# 06_Ethernet_Interface.net
KiCad netlist of a schematic drawn in Altium Designer
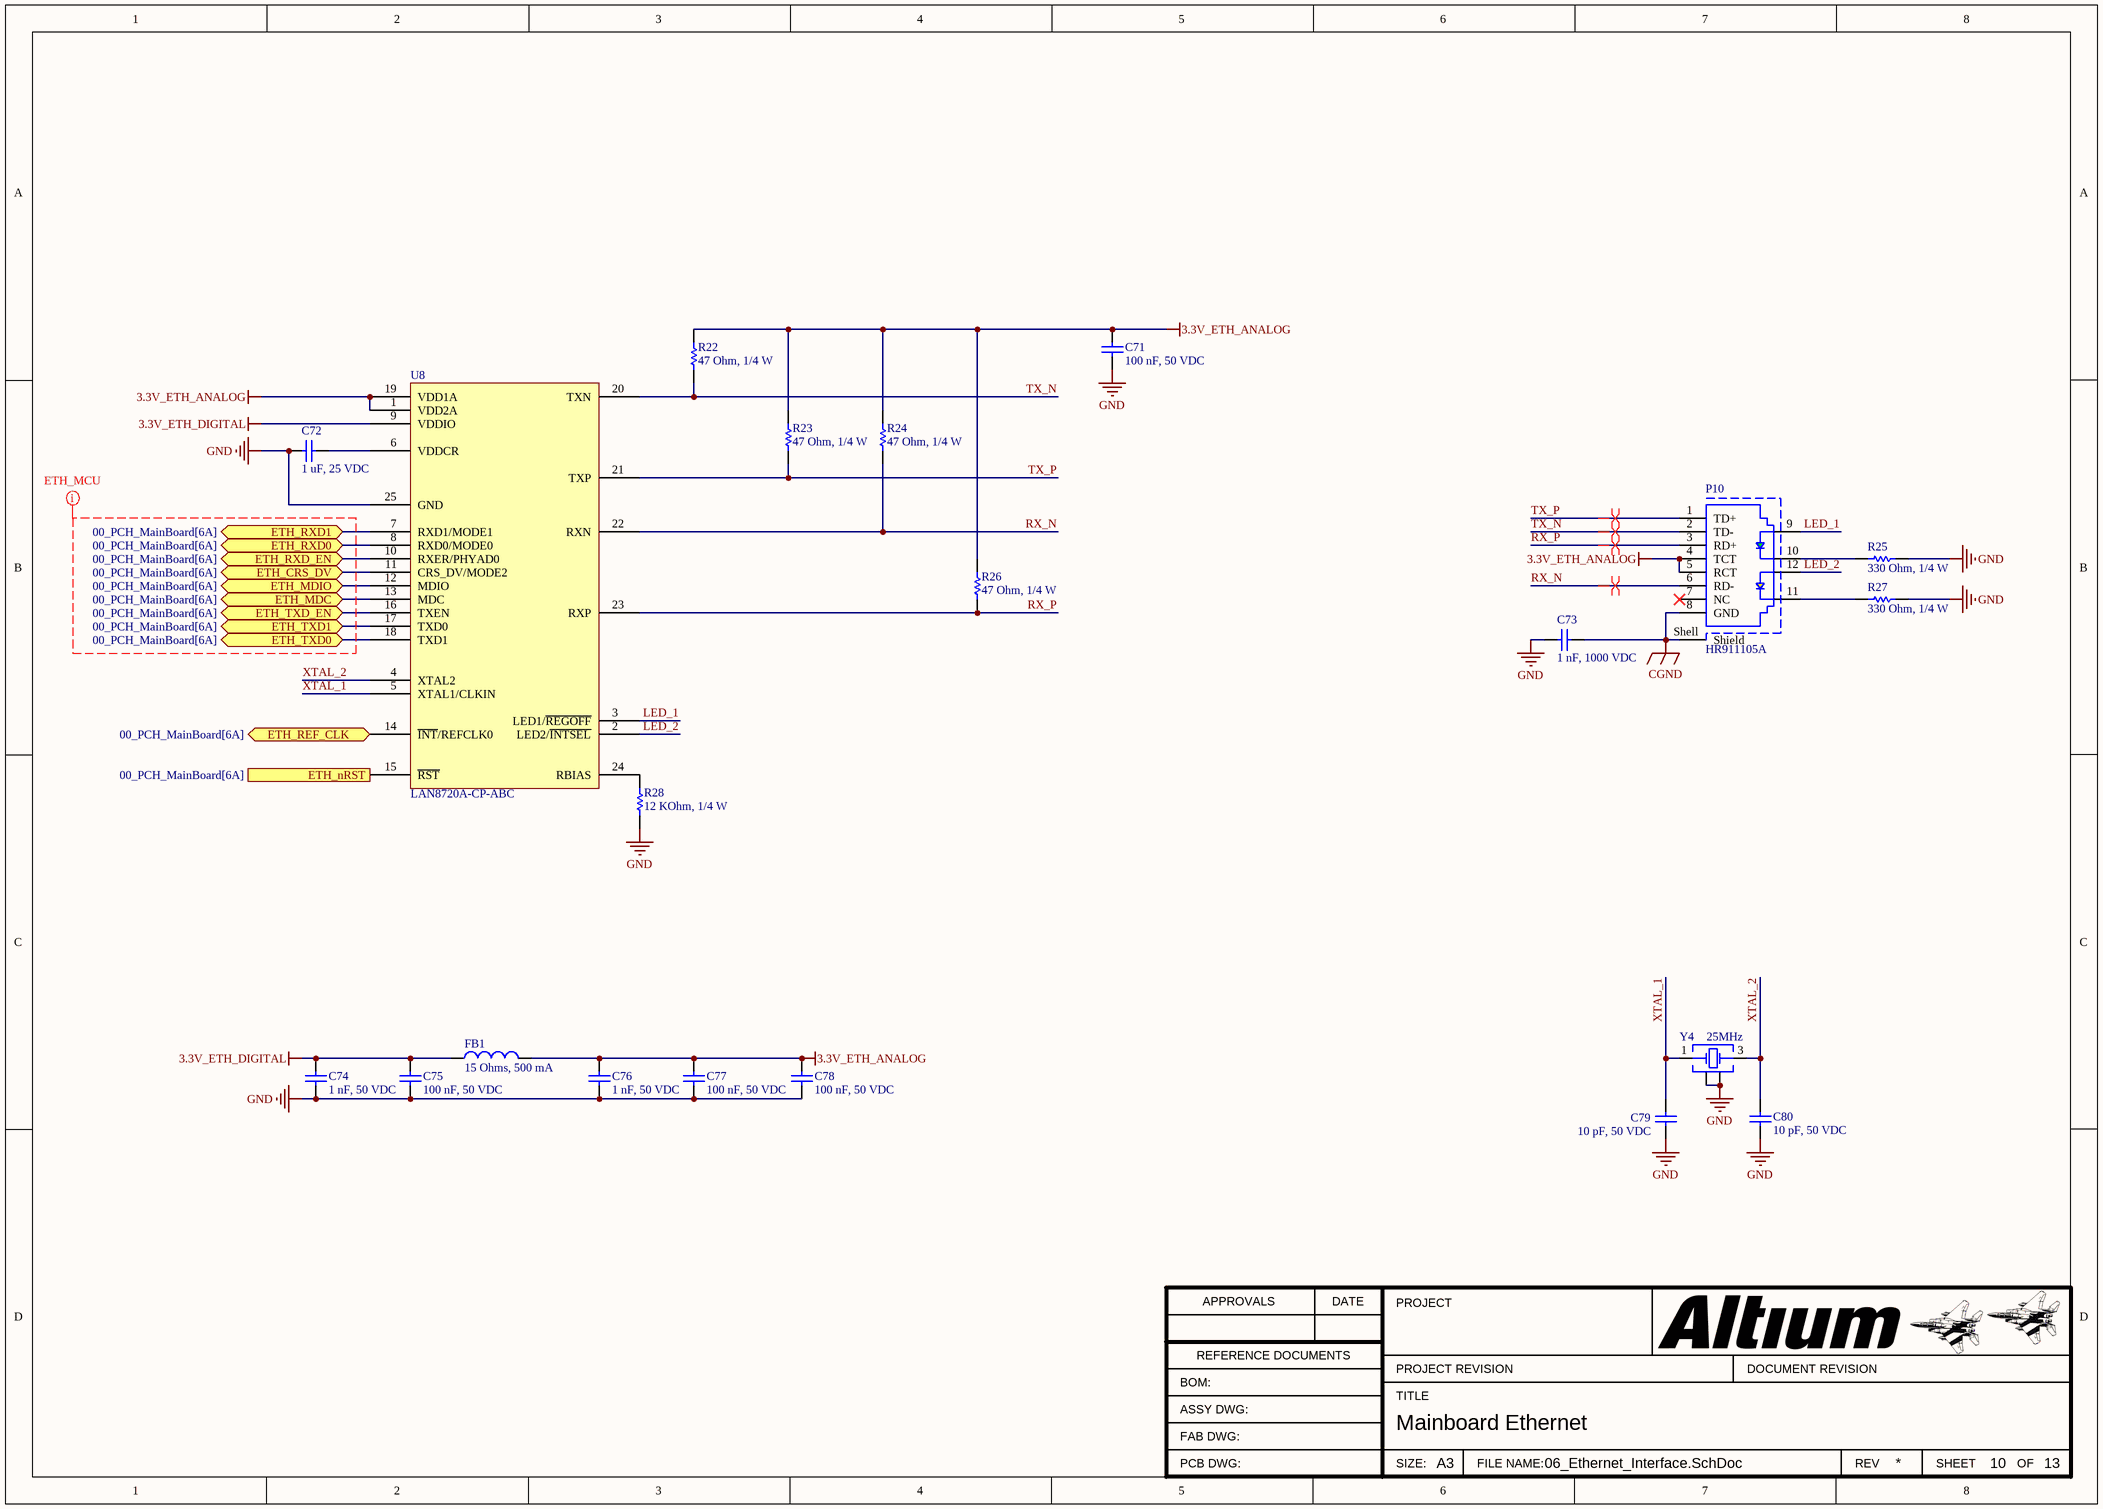
[diagram p0: 06_Ethernet_Interface.SchDoc]

(export (version "E")
  (design (tool "Eeschema 10.0.6"))
  (components
    (comp (ref "C71")
      (value "100 nF, 50 VDC")
      (footprint "CAP_0603")
      (description "CAP, size 0603, 100 nF, 50 VDC")
      (fields (field (name "TOLERANCE") "+/-10%"))
      (libsource (lib "Altium_Ceramic_Cap") (part "0106031041050"))
    )
    (comp (ref "C72")
      (value "1 uF, 25 VDC")
      (footprint "CAP_0603")
      (description "CAP, size 0603, 1 uF, 25 VDC")
      (fields (field (name "TOLERANCE") "+/-10%"))
      (libsource (lib "Altium_Ceramic_Cap") (part "0106031051025"))
    )
    (comp (ref "C73")
      (value "1 nF, 1000 VDC")
      (footprint "CAP1210")
      (description "CAP, size 1210, 1nF, 1000 VDC")
      (fields (field (name "TOLERANCE") "+/-10%"))
      (libsource (lib "Altium_Ceramic_Cap") (part "011210102101000"))
    )
    (comp (ref "C74")
      (value "1 nF, 50 VDC")
      (footprint "CAP_0603")
      (description "CAP, size 0603, 1 nF, 50 VDC")
      (fields (field (name "TOLERANCE") "+/-10%"))
      (libsource (lib "Altium_Ceramic_Cap") (part "0106031051050"))
    )
    (comp (ref "C75")
      (value "100 nF, 50 VDC")
      (footprint "CAP_0603")
      (description "CAP, size 0603, 100 nF, 50 VDC")
      (fields (field (name "TOLERANCE") "+/-10%"))
      (libsource (lib "Altium_Ceramic_Cap") (part "0106031041050"))
    )
    (comp (ref "C76")
      (value "1 nF, 50 VDC")
      (footprint "CAP_0603")
      (description "CAP, size 0603, 1 nF, 50 VDC")
      (fields (field (name "TOLERANCE") "+/-10%"))
      (libsource (lib "Altium_Ceramic_Cap") (part "0106031051050"))
    )
    (comp (ref "C77")
      (value "100 nF, 50 VDC")
      (footprint "CAP_0603")
      (description "CAP, size 0603, 100 nF, 50 VDC")
      (fields (field (name "TOLERANCE") "+/-10%"))
      (libsource (lib "Altium_Ceramic_Cap") (part "0106031041050"))
    )
    (comp (ref "C78")
      (value "100 nF, 50 VDC")
      (footprint "CAP_0603")
      (description "CAP, size 0603, 100 nF, 50 VDC")
      (fields (field (name "TOLERANCE") "+/-10%"))
      (libsource (lib "Altium_Ceramic_Cap") (part "0106031041050"))
    )
    (comp (ref "C79")
      (value "10 pF, 50 VDC")
      (footprint "CAP_0603")
      (description "CAP, size 0603, 10 pF, 50 VDC")
      (fields (field (name "TOLERANCE") "+/-5%"))
      (libsource (lib "Altium_Ceramic_Cap") (part "0106031000550"))
    )
    (comp (ref "C80")
      (value "10 pF, 50 VDC")
      (footprint "CAP_0603")
      (description "CAP, size 0603, 10 pF, 50 VDC")
      (fields (field (name "TOLERANCE") "+/-5%"))
      (libsource (lib "Altium_Ceramic_Cap") (part "0106031000550"))
    )
    (comp (ref "FB1")
      (value "15 Ohms, 500 mA")
      (footprint "FER_0603")
      (description "Ferrite, 0603, 15 Ohms, 500 mA")
      (fields (field (name "TOLERANCE") "+/-25%"))
      (libsource (lib "Altium_Ferrite_Bead") (part "03060315050125"))
    )
    (comp (ref "P10")
      (value "HR911105A")
      (footprint "HANRUN_HR911105A")
      (description "Single Port RJ45 Connector with Integrated Magnetics and LED")
      (libsource (lib "Altium_Other") (part "HANRUN_HR911105A"))
    )
    (comp (ref "R22")
      (value "47 Ohm, 1/4 W")
      (footprint "resistor_0603")
      (description "RES, size 0603, 47 Ohm, 1/4 W")
      (libsource (lib "Altium_Resistor") (part "0006034701"))
    )
    (comp (ref "R23")
      (value "47 Ohm, 1/4 W")
      (footprint "resistor_0603")
      (description "RES, size 0603, 47 Ohm, 1/4 W")
      (libsource (lib "Altium_Resistor") (part "0006034701"))
    )
    (comp (ref "R24")
      (value "47 Ohm, 1/4 W")
      (footprint "resistor_0603")
      (description "RES, size 0603, 47 Ohm, 1/4 W")
      (libsource (lib "Altium_Resistor") (part "0006034701"))
    )
    (comp (ref "R25")
      (value "330 Ohm, 1/4 W")
      (footprint "resistor_0603")
      (description "RES, size 0603, 330 Ohm, 1/4 W")
      (libsource (lib "Altium_Resistor") (part "0006033311"))
    )
    (comp (ref "R26")
      (value "47 Ohm, 1/4 W")
      (footprint "resistor_0603")
      (description "RES, size 0603, 47 Ohm, 1/4 W")
      (libsource (lib "Altium_Resistor") (part "0006034701"))
    )
    (comp (ref "R27")
      (value "330 Ohm, 1/4 W")
      (footprint "resistor_0603")
      (description "RES, size 0603, 330 Ohm, 1/4 W")
      (libsource (lib "Altium_Resistor") (part "0006033311"))
    )
    (comp (ref "R28")
      (value "12 KOhm, 1/4 W")
      (footprint "resistor_0603")
      (description "RES, size 0603, 12 KOhm, 1/4 W")
      (libsource (lib "Altium_Resistor") (part "0006031235"))
    )
    (comp (ref "U8")
      (value "LAN8720A-CP-ABC")
      (footprint "LAN8720A-CP-ABC")
      (description "Ethernet ICs Small Footprint RMII RMII 10/100 Ethernet")
      (fields (field (name "MANUFACTURER") "Microchip Technology"))
      (libsource (lib "Altium_MCU") (part "LAN8720A-CP-ABC"))
    )
    (comp (ref "Y4")
      (value "25MHz")
      (footprint "WE-XTAL_CFPX-180")
      (description "WE-XTAL Quartz Crystal, SMT, CFPX-180, 25MHz, +/-10ppm")
      (fields
        (field (name "MANUFACTURER PART NUMBER") "NX3225GA-25.000M-STD-CRG-1")
        (field (name "MANUFACTURER") "NDK")
      )
      (libsource (lib "Altium_XTAL") (part "073525256008"))
    )
  )
  (nets
    (net (code "1") (name "/ETH_CRS_DV") (class "Default")
      (node (ref "U8") (pin "11") (pinfunction "CRS_DV/MODE2_11") (pintype "passive"))
    )
    (net (code "2") (name "/ETH_MDC") (class "Default")
      (node (ref "U8") (pin "13") (pinfunction "MDC_13") (pintype "passive"))
    )
    (net (code "3") (name "/ETH_MDIO") (class "Default")
      (node (ref "U8") (pin "12") (pinfunction "MDIO_12") (pintype "passive"))
    )
    (net (code "4") (name "/ETH_REF_CLK") (class "Default")
      (node (ref "U8") (pin "14") (pinfunction "~{INT}/REFCLK0_14") (pintype "passive"))
    )
    (net (code "5") (name "/ETH_RXD0") (class "Default")
      (node (ref "U8") (pin "8") (pinfunction "RXD0/MODE0_8") (pintype "passive"))
    )
    (net (code "6") (name "/ETH_RXD1") (class "Default")
      (node (ref "U8") (pin "7") (pinfunction "RXD1/MODE1_7") (pintype "passive"))
    )
    (net (code "7") (name "/ETH_RXD_EN") (class "Default")
      (node (ref "U8") (pin "10") (pinfunction "RXER/PHYAD0_10") (pintype "passive"))
    )
    (net (code "8") (name "/ETH_TXD0") (class "Default")
      (node (ref "U8") (pin "18") (pinfunction "TXD1_18") (pintype "passive"))
    )
    (net (code "9") (name "/ETH_TXD1") (class "Default")
      (node (ref "U8") (pin "17") (pinfunction "TXD0_17") (pintype "passive"))
    )
    (net (code "10") (name "/ETH_TXD_EN") (class "Default")
      (node (ref "U8") (pin "16") (pinfunction "TXEN_16") (pintype "passive"))
    )
    (net (code "11") (name "/ETH_nRST") (class "Default")
      (node (ref "U8") (pin "15") (pinfunction "~{RST}_15") (pintype "passive"))
    )
    (net (code "12") (name "/LED_1") (class "Default")
      (node (ref "P10") (pin "9") (pinfunction "9_9") (pintype "passive"))
      (node (ref "U8") (pin "3") (pinfunction "LED1/~{REGOFF}_3") (pintype "passive"))
    )
    (net (code "13") (name "/LED_2") (class "Default")
      (node (ref "P10") (pin "12") (pinfunction "12_12") (pintype "passive"))
      (node (ref "U8") (pin "2") (pinfunction "LED2/~{INTSEL}_2") (pintype "passive"))
    )
    (net (code "14") (name "/RX_N") (class "Default")
      (node (ref "P10") (pin "6") (pinfunction "RD-_6") (pintype "passive"))
      (node (ref "R24") (pin "1") (pinfunction "1_1") (pintype "passive"))
      (node (ref "U8") (pin "22") (pinfunction "RXN_22") (pintype "passive"))
    )
    (net (code "15") (name "/RX_P") (class "Default")
      (node (ref "P10") (pin "3") (pinfunction "RD+_3") (pintype "passive"))
      (node (ref "R26") (pin "1") (pinfunction "1_1") (pintype "passive"))
      (node (ref "U8") (pin "23") (pinfunction "RXP_23") (pintype "passive"))
    )
    (net (code "16") (name "/TX_N") (class "Default")
      (node (ref "P10") (pin "2") (pinfunction "TD-_2") (pintype "passive"))
      (node (ref "R22") (pin "1") (pinfunction "1_1") (pintype "passive"))
      (node (ref "U8") (pin "20") (pinfunction "TXN_20") (pintype "passive"))
    )
    (net (code "17") (name "/TX_P") (class "Default")
      (node (ref "P10") (pin "1") (pinfunction "TD+_1") (pintype "passive"))
      (node (ref "R23") (pin "1") (pinfunction "1_1") (pintype "passive"))
      (node (ref "U8") (pin "21") (pinfunction "TXP_21") (pintype "passive"))
    )
    (net (code "18") (name "/XTAL_1") (class "Default")
      (node (ref "C79") (pin "2") (pinfunction "2_2") (pintype "passive"))
      (node (ref "U8") (pin "5") (pinfunction "XTAL1/CLKIN_5") (pintype "passive"))
      (node (ref "Y4") (pin "1") (pinfunction "Crystal_1") (pintype "passive"))
    )
    (net (code "19") (name "/XTAL_2") (class "Default")
      (node (ref "C80") (pin "2") (pinfunction "2_2") (pintype "passive"))
      (node (ref "U8") (pin "4") (pinfunction "XTAL2_4") (pintype "passive"))
      (node (ref "Y4") (pin "3") (pinfunction "Crystal_3") (pintype "passive"))
    )
    (net (code "20") (name "3.3V_ETH_ANALOG") (class "Default")
      (node (ref "C71") (pin "2") (pinfunction "2_2") (pintype "passive"))
      (node (ref "C76") (pin "2") (pinfunction "2_2") (pintype "passive"))
      (node (ref "C77") (pin "2") (pinfunction "2_2") (pintype "passive"))
      (node (ref "C78") (pin "2") (pinfunction "2_2") (pintype "passive"))
      (node (ref "FB1") (pin "2") (pinfunction "2_2") (pintype "passive"))
      (node (ref "P10") (pin "4") (pinfunction "TCT_4") (pintype "passive"))
      (node (ref "P10") (pin "5") (pinfunction "RCT_5") (pintype "passive"))
      (node (ref "R22") (pin "2") (pinfunction "2_2") (pintype "passive"))
      (node (ref "R23") (pin "2") (pinfunction "2_2") (pintype "passive"))
      (node (ref "R24") (pin "2") (pinfunction "2_2") (pintype "passive"))
      (node (ref "R26") (pin "2") (pinfunction "2_2") (pintype "passive"))
      (node (ref "U8") (pin "1") (pinfunction "VDD2A_1") (pintype "passive"))
      (node (ref "U8") (pin "19") (pinfunction "VDD1A_19") (pintype "passive"))
    )
    (net (code "21") (name "3.3V_ETH_DIGITAL") (class "Default")
      (node (ref "C74") (pin "2") (pinfunction "2_2") (pintype "passive"))
      (node (ref "C75") (pin "2") (pinfunction "2_2") (pintype "passive"))
      (node (ref "FB1") (pin "1") (pinfunction "1_1") (pintype "passive"))
      (node (ref "U8") (pin "9") (pinfunction "VDDIO_9") (pintype "passive"))
    )
    (net (code "22") (name "CGND") (class "Default")
      (node (ref "C73") (pin "2") (pinfunction "2_2") (pintype "passive"))
      (node (ref "P10") (pin "8") (pinfunction "GND_8") (pintype "passive"))
      (node (ref "P10") (pin "Shell") (pinfunction "Shield_Shell") (pintype "passive"))
    )
    (net (code "23") (name "GND") (class "Default")
      (node (ref "C71") (pin "1") (pinfunction "1_1") (pintype "passive"))
      (node (ref "C72") (pin "1") (pinfunction "1_1") (pintype "passive"))
      (node (ref "C73") (pin "1") (pinfunction "1_1") (pintype "passive"))
      (node (ref "C74") (pin "1") (pinfunction "1_1") (pintype "passive"))
      (node (ref "C75") (pin "1") (pinfunction "1_1") (pintype "passive"))
      (node (ref "C76") (pin "1") (pinfunction "1_1") (pintype "passive"))
      (node (ref "C77") (pin "1") (pinfunction "1_1") (pintype "passive"))
      (node (ref "C78") (pin "1") (pinfunction "1_1") (pintype "passive"))
      (node (ref "C79") (pin "1") (pinfunction "1_1") (pintype "passive"))
      (node (ref "C80") (pin "1") (pinfunction "1_1") (pintype "passive"))
      (node (ref "R25") (pin "2") (pinfunction "2_2") (pintype "passive"))
      (node (ref "R27") (pin "2") (pinfunction "2_2") (pintype "passive"))
      (node (ref "R28") (pin "1") (pinfunction "1_1") (pintype "passive"))
      (node (ref "U8") (pin "25") (pinfunction "GND_25") (pintype "passive"))
      (node (ref "Y4") (pin "2") (pinfunction "GND_2") (pintype "passive"))
      (node (ref "Y4") (pin "4") (pinfunction "GND_4") (pintype "passive"))
    )
    (net (code "24") (name "Net-(P10-Pad10)") (class "Default")
      (node (ref "P10") (pin "10") (pinfunction "10_10") (pintype "passive"))
      (node (ref "R25") (pin "1") (pinfunction "1_1") (pintype "passive"))
    )
    (net (code "25") (name "Net-(P10-Pad11)") (class "Default")
      (node (ref "P10") (pin "11") (pinfunction "11_11") (pintype "passive"))
      (node (ref "R27") (pin "1") (pinfunction "1_1") (pintype "passive"))
    )
    (net (code "26") (name "Net-(U8-RBIAS)") (class "Default")
      (node (ref "R28") (pin "2") (pinfunction "2_2") (pintype "passive"))
      (node (ref "U8") (pin "24") (pinfunction "RBIAS_24") (pintype "passive"))
    )
    (net (code "27") (name "Net-(U8-VDDCR)") (class "Default")
      (node (ref "C72") (pin "2") (pinfunction "2_2") (pintype "passive"))
      (node (ref "U8") (pin "6") (pinfunction "VDDCR_6") (pintype "passive"))
    )
    (net (code "28") (name "unconnected-(P10-NC-Pad7)") (class "Default")
      (node (ref "P10") (pin "7") (pinfunction "NC_7") (pintype "passive+no_connect"))
    )
  )
)
